# Micro.net
KiCad netlist of a schematic drawn in Altium Designer
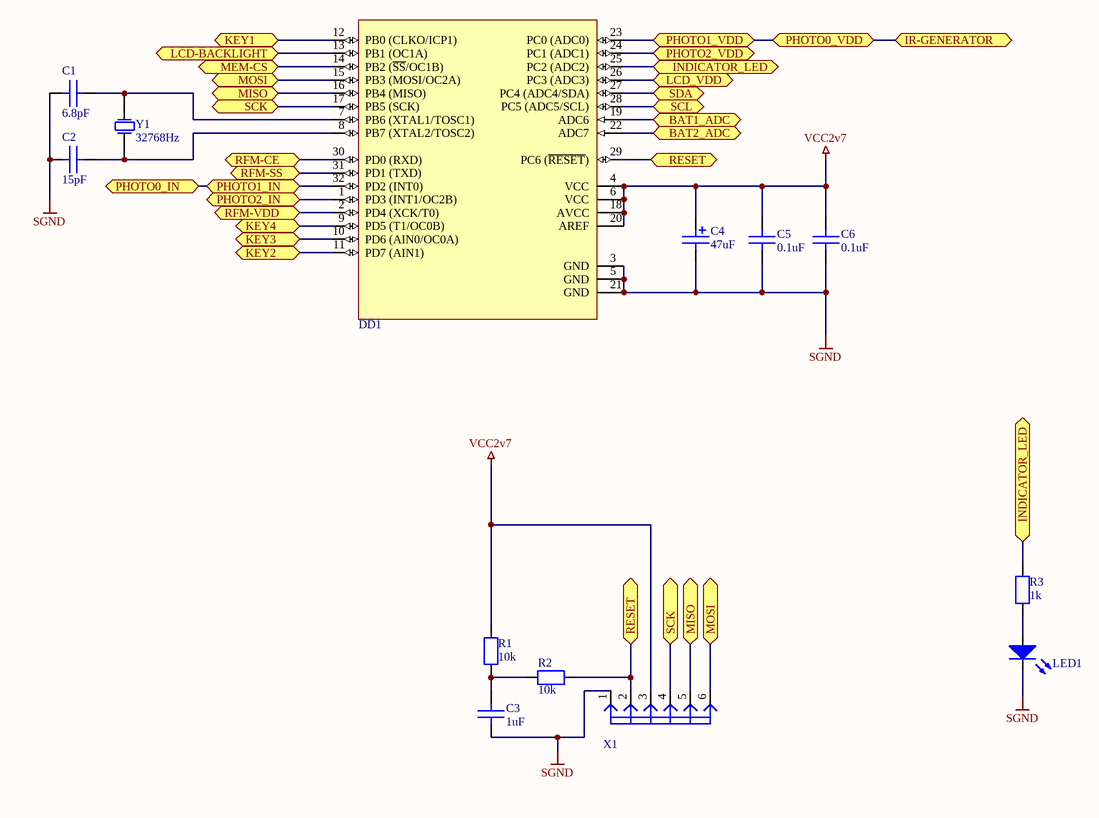
[diagram p0: Micro.SchDoc]

(export (version "E")
  (design (tool "Eeschema 10.0.6"))
  (components
    (comp (ref "C1")
      (value "6.8pF")
      (footprint "C0805")
      (description "C6.8pF-50V-10%")
      (fields (field (name "VOLTAGE") "50V"))
      (libsource (lib "MCounter_Common") (part "C6.8pF-50V-10%"))
    )
    (comp (ref "C2")
      (value "15pF")
      (footprint "C0805")
      (description "C15pF-50V-10%")
      (fields (field (name "VOLTAGE") "50V"))
      (libsource (lib "MCounter_Common") (part "C15pF-50V-10%"))
    )
    (comp (ref "C3")
      (value "1uF")
      (footprint "C0805")
      (description "C1uF-50V")
      (fields (field (name "VOLTAGE") "50V"))
      (libsource (lib "MCounter_Common") (part "C1uF-50V"))
    )
    (comp (ref "C4")
      (value "47uF")
      (footprint "TC2917")
      (description "C47uF-10V-tant")
      (fields (field (name "VOLTAGE") "10V"))
      (libsource (lib "MCounter_Common") (part "C47uF-10V-tant"))
    )
    (comp (ref "C5")
      (value "0.1uF")
      (footprint "C0805")
      (description "C0.1uF-50V")
      (fields (field (name "VOLTAGE") "50V"))
      (libsource (lib "MCounter_Common") (part "C0.1uF-50V"))
    )
    (comp (ref "C6")
      (value "0.1uF")
      (footprint "C0805")
      (description "C0.1uF-50V")
      (fields (field (name "VOLTAGE") "50V"))
      (libsource (lib "MCounter_Common") (part "C0.1uF-50V"))
    )
    (comp (ref "DD1")
      (value "ATmega328P")
      (footprint "32A_N")
      (description "8-Bit AVR Microcontroller with 32K Bytes of In-System Programmable Flash Memory")
      (libsource (lib "MCounter_Common") (part "ATmega328P"))
    )
    (comp (ref "LED1")
      (value "LED-RED")
      (footprint "LED-3")
      (description "LED red")
      (libsource (lib "MCounter_Common") (part "LED-RED"))
    )
    (comp (ref "R1")
      (value "10k")
      (footprint "R0805")
      (description "R-10k-5%")
      (fields (field (name "Comment") "R10k-5%"))
      (libsource (lib "") (part "R10k-5%_1"))
    )
    (comp (ref "R2")
      (value "10k")
      (footprint "R0805")
      (description "R-10k-5%")
      (fields (field (name "Comment") "R10k-5%"))
      (libsource (lib "MCounter_Common") (part "R10k-5%"))
    )
    (comp (ref "R3")
      (value "1k")
      (footprint "R0805")
      (description "R-1k-5%")
      (fields (field (name "Comment") "R1k-5%"))
      (libsource (lib "MCounter_Common") (part "R1k-5%"))
    )
    (comp (ref "X1") (value "PLS-6") (footprint "PLS-6") (libsource (lib "MCounter_Common") (part "PLS-6")))
    (comp (ref "Y1")
      (value "32768Hz")
      (footprint "KX38")
      (description "Crystal Oscillator 32768Hz")
      (fields (field (name "Comment") "XTAL32768Hz"))
      (libsource (lib "MCounter_Common") (part "XTAL32768Hz"))
    )
  )
  (nets
    (net (code "1") (name "/BAT1_ADC") (class "Default")
      (node (ref "DD1") (pin "19") (pinfunction "ADC6_19") (pintype "input"))
    )
    (net (code "2") (name "/BAT2_ADC") (class "Default")
      (node (ref "DD1") (pin "22") (pinfunction "ADC7_22") (pintype "input"))
    )
    (net (code "3") (name "/INDICATOR_LED") (class "Default")
      (node (ref "DD1") (pin "25") (pinfunction "PC2_(ADC2)_25") (pintype "bidirectional"))
      (node (ref "R3") (pin "2") (pinfunction "2_2") (pintype "passive"))
    )
    (net (code "4") (name "/IR-GENERATOR") (class "Default")
      (node (ref "DD1") (pin "23") (pinfunction "PC0_(ADC0)_23") (pintype "bidirectional"))
    )
    (net (code "5") (name "/KEY1") (class "Default")
      (node (ref "DD1") (pin "12") (pinfunction "PB0_(CLKO/ICP1)_12") (pintype "bidirectional"))
    )
    (net (code "6") (name "/KEY2") (class "Default")
      (node (ref "DD1") (pin "11") (pinfunction "PD7_(AIN1)_11") (pintype "bidirectional"))
    )
    (net (code "7") (name "/KEY3") (class "Default")
      (node (ref "DD1") (pin "10") (pinfunction "PD6_(AIN0/OC0A)_10") (pintype "bidirectional"))
    )
    (net (code "8") (name "/KEY4") (class "Default")
      (node (ref "DD1") (pin "9") (pinfunction "PD5_(T1/OC0B)_9") (pintype "bidirectional"))
    )
    (net (code "9") (name "/LCD-BACKLIGHT") (class "Default")
      (node (ref "DD1") (pin "13") (pinfunction "PB1_(OC1A)_13") (pintype "bidirectional"))
    )
    (net (code "10") (name "/LCD_VDD") (class "Default")
      (node (ref "DD1") (pin "26") (pinfunction "PC3_(ADC3)_26") (pintype "bidirectional"))
    )
    (net (code "11") (name "/MEM-CS") (class "Default")
      (node (ref "DD1") (pin "14") (pinfunction "PB2_(~{SS}/OC1B)_14") (pintype "bidirectional"))
    )
    (net (code "12") (name "/MISO") (class "Default")
      (node (ref "DD1") (pin "16") (pinfunction "PB4_(MISO)_16") (pintype "bidirectional"))
      (node (ref "X1") (pin "5") (pinfunction "5_5") (pintype "passive"))
    )
    (net (code "13") (name "/MOSI") (class "Default")
      (node (ref "DD1") (pin "15") (pinfunction "PB3_(MOSI/OC2A)_15") (pintype "bidirectional"))
      (node (ref "X1") (pin "6") (pinfunction "6_6") (pintype "passive"))
    )
    (net (code "14") (name "/PHOTO0_IN") (class "Default")
      (node (ref "DD1") (pin "32") (pinfunction "PD2_(INT0)_32") (pintype "bidirectional"))
    )
    (net (code "15") (name "/PHOTO2_IN") (class "Default")
      (node (ref "DD1") (pin "1") (pinfunction "PD3_(INT1/OC2B)_1") (pintype "bidirectional"))
    )
    (net (code "16") (name "/PHOTO2_VDD") (class "Default")
      (node (ref "DD1") (pin "24") (pinfunction "PC1_(ADC1)_24") (pintype "bidirectional"))
    )
    (net (code "17") (name "/RESET") (class "Default")
      (node (ref "DD1") (pin "29") (pinfunction "PC6_(~{RESET})_29") (pintype "bidirectional"))
      (node (ref "R2") (pin "2") (pinfunction "2_2") (pintype "passive"))
      (node (ref "X1") (pin "2") (pinfunction "2_2") (pintype "passive"))
    )
    (net (code "18") (name "/RFM-CE") (class "Default")
      (node (ref "DD1") (pin "30") (pinfunction "PD0_(RXD)_30") (pintype "bidirectional"))
    )
    (net (code "19") (name "/RFM-SS") (class "Default")
      (node (ref "DD1") (pin "31") (pinfunction "PD1_(TXD)_31") (pintype "bidirectional"))
    )
    (net (code "20") (name "/RFM-VDD") (class "Default")
      (node (ref "DD1") (pin "2") (pinfunction "PD4_(XCK/T0)_2") (pintype "bidirectional"))
    )
    (net (code "21") (name "/SCK") (class "Default")
      (node (ref "DD1") (pin "17") (pinfunction "PB5_(SCK)_17") (pintype "bidirectional"))
      (node (ref "X1") (pin "4") (pinfunction "4_4") (pintype "passive"))
    )
    (net (code "22") (name "/SCL") (class "Default")
      (node (ref "DD1") (pin "28") (pinfunction "PC5_(ADC5/SCL)_28") (pintype "bidirectional"))
    )
    (net (code "23") (name "/SDA") (class "Default")
      (node (ref "DD1") (pin "27") (pinfunction "PC4_(ADC4/SDA)_27") (pintype "bidirectional"))
    )
    (net (code "24") (name "Net-(C3-Pad2)") (class "Default")
      (node (ref "C3") (pin "2") (pinfunction "2_2") (pintype "passive"))
      (node (ref "R1") (pin "1") (pinfunction "1_1") (pintype "passive"))
      (node (ref "R2") (pin "1") (pinfunction "1_1") (pintype "passive"))
    )
    (net (code "25") (name "Net-(DD1-PB6_(XTAL1{slash}TOSC1))") (class "Default")
      (node (ref "C1") (pin "2") (pinfunction "2_2") (pintype "passive"))
      (node (ref "DD1") (pin "7") (pinfunction "PB6_(XTAL1/TOSC1)_7") (pintype "bidirectional"))
      (node (ref "Y1") (pin "2") (pinfunction "OSC2_2") (pintype "passive"))
    )
    (net (code "26") (name "Net-(DD1-PB7_(XTAL2{slash}TOSC2))") (class "Default")
      (node (ref "C2") (pin "2") (pinfunction "2_2") (pintype "passive"))
      (node (ref "DD1") (pin "8") (pinfunction "PB7_(XTAL2/TOSC2)_8") (pintype "bidirectional"))
      (node (ref "Y1") (pin "1") (pinfunction "OSC1_1") (pintype "passive"))
    )
    (net (code "27") (name "Net-(LED1-A)") (class "Default")
      (node (ref "LED1") (pin "1") (pinfunction "A_1") (pintype "passive"))
      (node (ref "R3") (pin "1") (pinfunction "1_1") (pintype "passive"))
    )
    (net (code "28") (name "SGND") (class "Default")
      (node (ref "C1") (pin "1") (pinfunction "1_1") (pintype "passive"))
      (node (ref "C2") (pin "1") (pinfunction "1_1") (pintype "passive"))
      (node (ref "C3") (pin "1") (pinfunction "1_1") (pintype "passive"))
      (node (ref "C4") (pin "2") (pinfunction "2_2") (pintype "passive"))
      (node (ref "C5") (pin "1") (pinfunction "1_1") (pintype "passive"))
      (node (ref "C6") (pin "1") (pinfunction "1_1") (pintype "passive"))
      (node (ref "DD1") (pin "21") (pinfunction "GND_21") (pintype "power_in"))
      (node (ref "DD1") (pin "3") (pinfunction "GND_3") (pintype "power_in"))
      (node (ref "DD1") (pin "5") (pinfunction "GND_5") (pintype "power_in"))
      (node (ref "LED1") (pin "2") (pinfunction "K_2") (pintype "passive"))
      (node (ref "X1") (pin "1") (pinfunction "1_1") (pintype "passive"))
    )
    (net (code "29") (name "VCC2v7") (class "Default")
      (node (ref "C4") (pin "1") (pinfunction "1_1") (pintype "passive"))
      (node (ref "C5") (pin "2") (pinfunction "2_2") (pintype "passive"))
      (node (ref "C6") (pin "2") (pinfunction "2_2") (pintype "passive"))
      (node (ref "DD1") (pin "18") (pinfunction "AVCC_18") (pintype "power_in"))
      (node (ref "DD1") (pin "20") (pinfunction "AREF_20") (pintype "passive"))
      (node (ref "DD1") (pin "4") (pinfunction "VCC_4") (pintype "power_in"))
      (node (ref "DD1") (pin "6") (pinfunction "VCC_6") (pintype "power_in"))
      (node (ref "R1") (pin "2") (pinfunction "2_2") (pintype "passive"))
      (node (ref "X1") (pin "3") (pinfunction "3_3") (pintype "passive"))
    )
  )
)
